# FlySky_Voltage_Sensor_PCB.net
KiCad netlist of a schematic drawn in Altium Designer
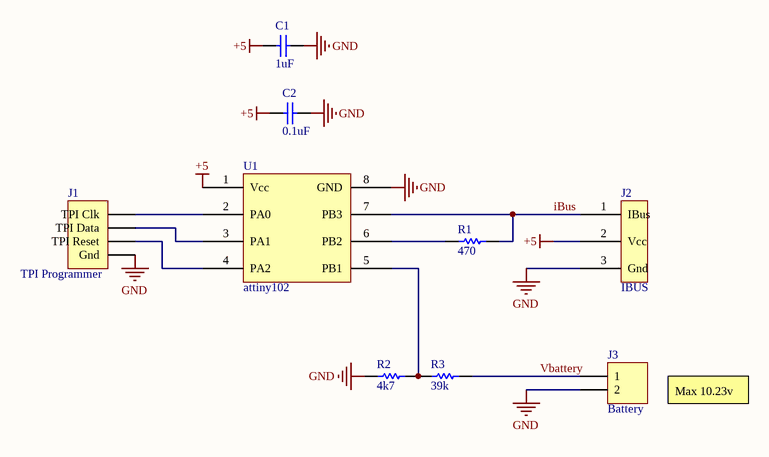
[diagram p0: FlySky Voltage Sensor PCB.SchDoc]

(export (version "E")
  (design (tool "Eeschema 10.0.6"))
  (components
    (comp (ref "C1")
      (value "1uF")
      (footprint "Cap SMD 0805A")
      (description "Capacitor")
      (fields (field (name "Comment") "Cap") (field (name "PUBLISHER") "Altium Limited"))
      (libsource (lib "Custom") (part "Cap"))
    )
    (comp (ref "C2")
      (value "0.1uF")
      (footprint "Cap SMD 0805A")
      (description "Capacitor")
      (fields (field (name "Comment") "Cap") (field (name "PUBLISHER") "Altium Limited"))
      (libsource (lib "Custom") (part "Cap"))
    )
    (comp (ref "J1")
      (value "TPI Programmer")
      (footprint "HDR1X4")
      (description "Header, 4-Pin")
      (fields (field (name "PUBLISHER") "Altium Limited"))
      (libsource (lib "Miscellaneous Connectors") (part "Header 4"))
    )
    (comp (ref "J2") (value "IBUS") (footprint "HDR3") (libsource (lib "Custom") (part "SIP3 CONNECTOR")))
    (comp (ref "J3")
      (value "Battery")
      (footprint "HDR1X2")
      (description "Header, 2-Pin")
      (fields (field (name "PUBLISHER") "Altium Limited"))
      (libsource (lib "Miscellaneous Connectors") (part "Header 2"))
    )
    (comp (ref "R1")
      (value "470")
      (footprint "Res SMD 0805A")
      (fields (field (name "Comment") "Res1"))
      (libsource (lib "Custom") (part "Resistor"))
    )
    (comp (ref "R2")
      (value "4k7")
      (footprint "Res SMD 0805A")
      (fields (field (name "Comment") "Res1"))
      (libsource (lib "Custom") (part "Resistor"))
    )
    (comp (ref "R3")
      (value "39k")
      (footprint "Res SMD 0805A")
      (fields (field (name "Comment") "Res1"))
      (libsource (lib "Custom") (part "Resistor"))
    )
    (comp (ref "U1") (value "attiny102") (footprint "SOIC8") (libsource (lib "Custom") (part "attiny102")))
  )
  (nets
    (net (code "1") (name "+5") (class "Default")
      (node (ref "C1") (pin "2") (pinfunction "2_2") (pintype "passive"))
      (node (ref "C2") (pin "2") (pinfunction "2_2") (pintype "passive"))
      (node (ref "J2") (pin "2") (pinfunction "Vcc_2") (pintype "passive"))
      (node (ref "U1") (pin "1") (pinfunction "Vcc_1") (pintype "passive"))
    )
    (net (code "2") (name "/Vbattery") (class "Default")
      (node (ref "J3") (pin "1") (pinfunction "1_1") (pintype "passive"))
      (node (ref "R3") (pin "1") (pinfunction "1_1") (pintype "passive"))
    )
    (net (code "3") (name "/iBus") (class "Default")
      (node (ref "J2") (pin "1") (pinfunction "IBus_1") (pintype "passive"))
      (node (ref "R1") (pin "1") (pinfunction "1_1") (pintype "passive"))
      (node (ref "U1") (pin "7") (pinfunction "PB3_7") (pintype "passive"))
    )
    (net (code "4") (name "GND") (class "Default")
      (node (ref "C1") (pin "1") (pinfunction "1_1") (pintype "passive"))
      (node (ref "C2") (pin "1") (pinfunction "1_1") (pintype "passive"))
      (node (ref "J1") (pin "4") (pinfunction "Gnd_4") (pintype "passive"))
      (node (ref "J2") (pin "3") (pinfunction "Gnd_3") (pintype "passive"))
      (node (ref "J3") (pin "2") (pinfunction "2_2") (pintype "passive"))
      (node (ref "R2") (pin "2") (pinfunction "2_2") (pintype "passive"))
      (node (ref "U1") (pin "8") (pinfunction "GND_8") (pintype "passive"))
    )
    (net (code "5") (name "Net-(J1-TPI_Clk)") (class "Default")
      (node (ref "J1") (pin "1") (pinfunction "TPI_Clk_1") (pintype "passive"))
      (node (ref "U1") (pin "2") (pinfunction "PA0_2") (pintype "passive"))
    )
    (net (code "6") (name "Net-(J1-TPI_Data)") (class "Default")
      (node (ref "J1") (pin "2") (pinfunction "TPI_Data_2") (pintype "passive"))
      (node (ref "U1") (pin "3") (pinfunction "PA1_3") (pintype "passive"))
    )
    (net (code "7") (name "Net-(J1-TPI_Reset)") (class "Default")
      (node (ref "J1") (pin "3") (pinfunction "TPI_Reset_3") (pintype "passive"))
      (node (ref "U1") (pin "4") (pinfunction "PA2_4") (pintype "passive"))
    )
    (net (code "8") (name "Net-(U1-PB1)") (class "Default")
      (node (ref "R2") (pin "1") (pinfunction "1_1") (pintype "passive"))
      (node (ref "R3") (pin "2") (pinfunction "2_2") (pintype "passive"))
      (node (ref "U1") (pin "5") (pinfunction "PB1_5") (pintype "passive"))
    )
    (net (code "9") (name "Net-(U1-PB2)") (class "Default")
      (node (ref "R1") (pin "2") (pinfunction "2_2") (pintype "passive"))
      (node (ref "U1") (pin "6") (pinfunction "PB2_6") (pintype "passive"))
    )
  )
)
